# KMO_IO_MV2_9_min.net
KiCad netlist of a schematic drawn in EAGLE
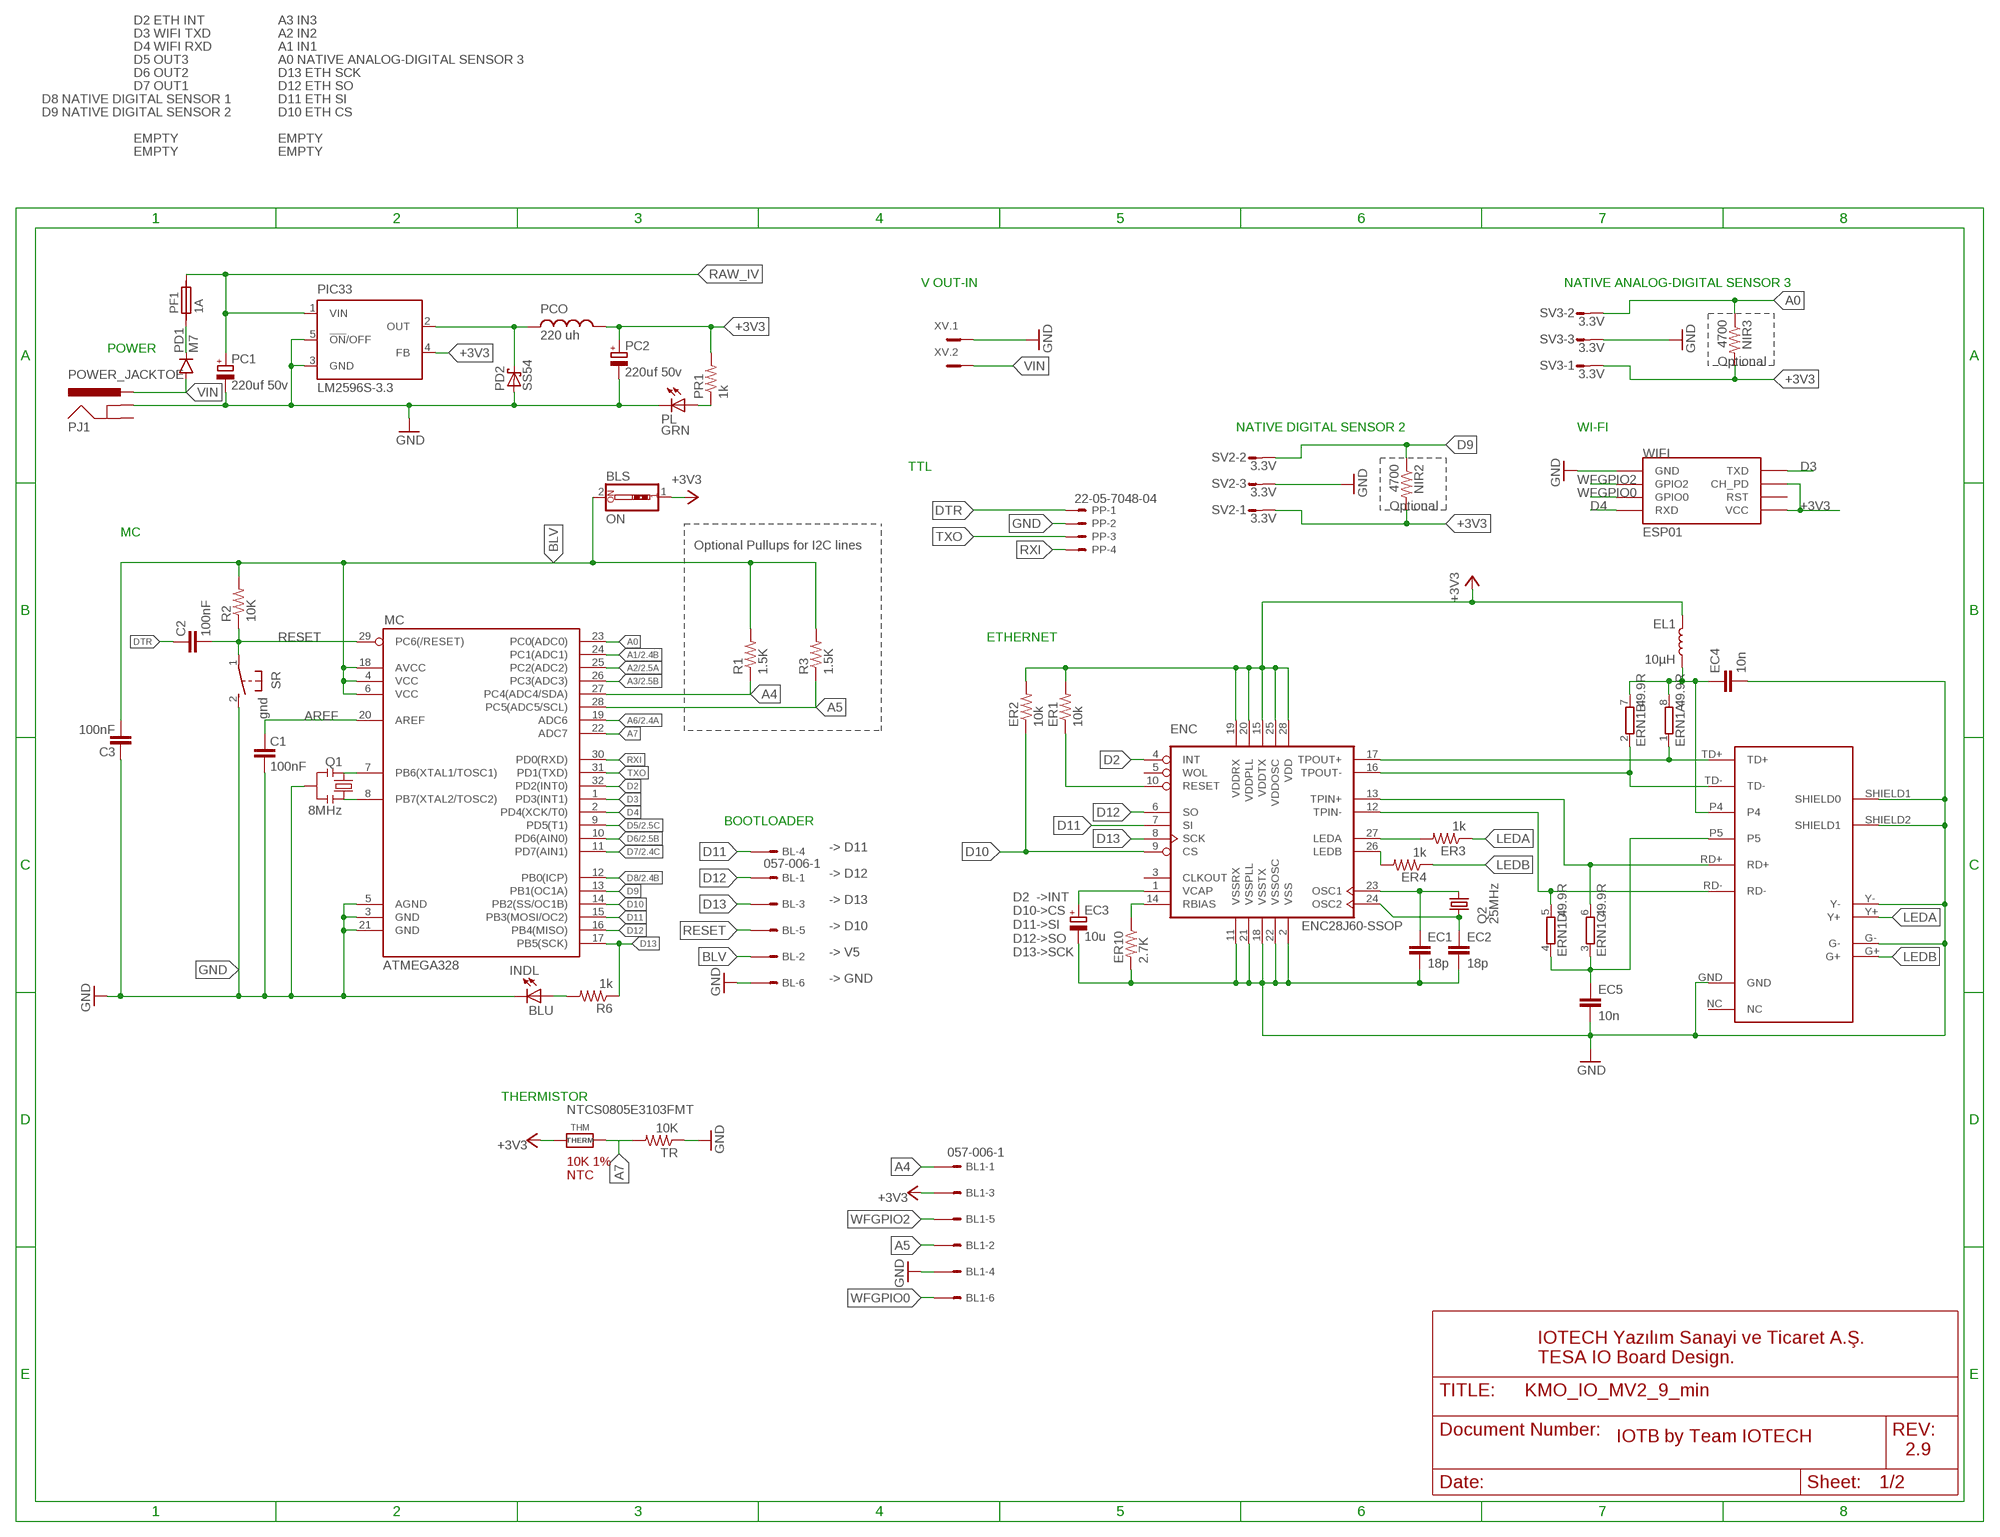
[diagram p0: schematic, sheet 1]
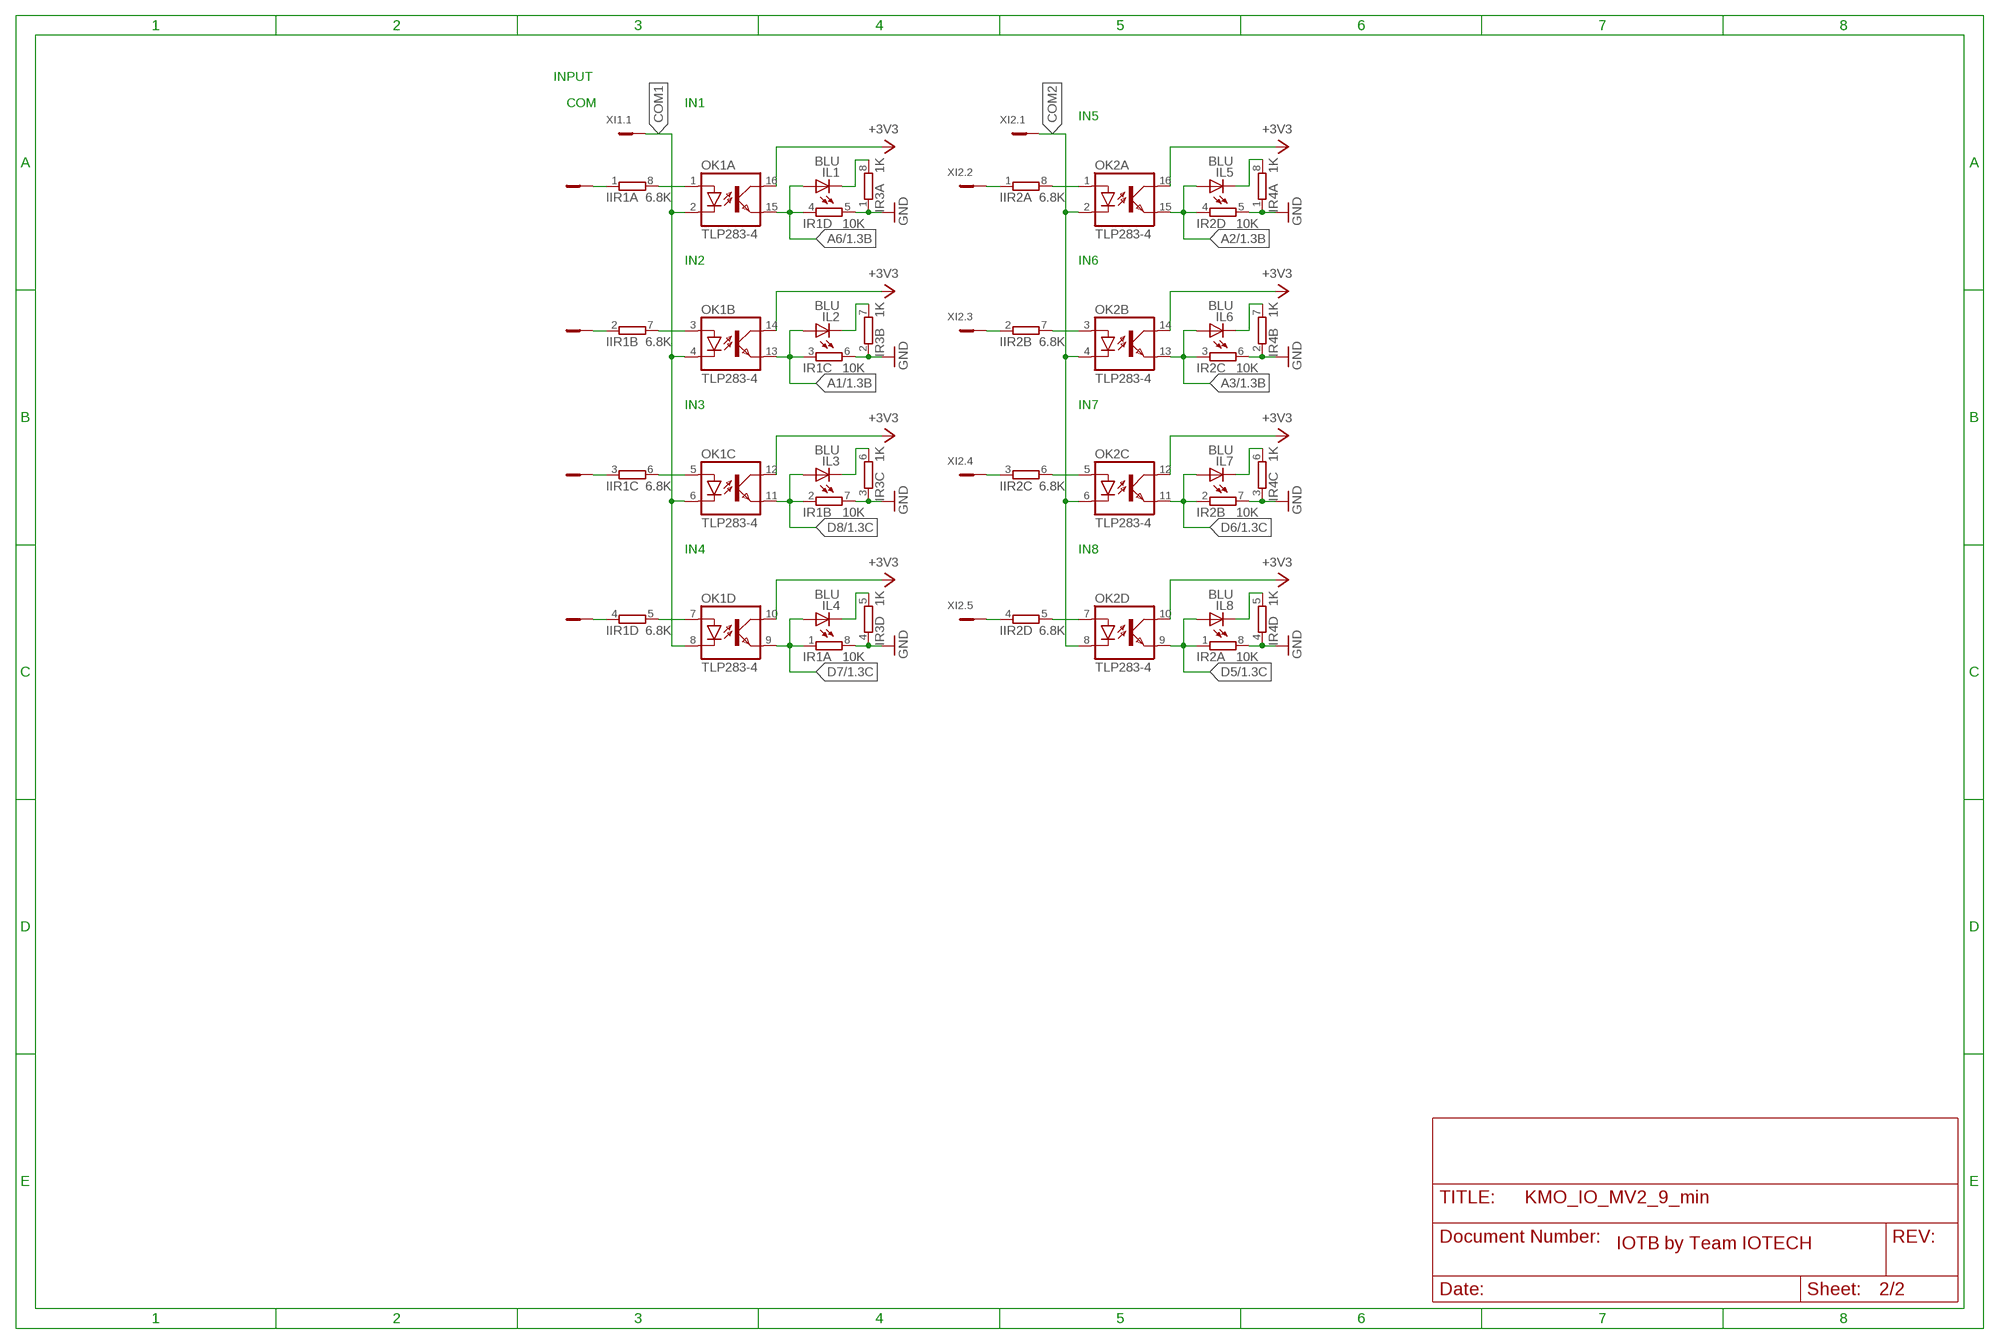
[diagram p1: schematic, sheet 2]

(export (version "E")
  (design (tool "Eeschema 10.0.6"))
  (components
    (comp (ref "BL")
      (value "057-006-1")
      (footprint "eagle-import:057-006-1")
      (libsource (lib "eagle-import") (part "057-006-1"))
    )
    (comp (ref "BL1")
      (value "057-006-1")
      (footprint "eagle-import:057-006-1")
      (libsource (lib "eagle-import") (part "057-006-1"))
    )
    (comp (ref "BLS")
      (value "ON")
      (footprint "eagle-import:EDG-01")
      (libsource (lib "eagle-import") (part "SW_DIP-1"))
    )
    (comp (ref "C1")
      (value "100nF")
      (footprint "eagle-import:0805")
      (libsource (lib "eagle-import") (part "CAP0805"))
    )
    (comp (ref "C2")
      (value "100nF")
      (footprint "eagle-import:0805")
      (libsource (lib "eagle-import") (part "CAP0805"))
    )
    (comp (ref "C3")
      (value "100nF")
      (footprint "eagle-import:0805")
      (libsource (lib "eagle-import") (part "CAP0805"))
    )
    (comp (ref "EC1")
      (value "18p")
      (footprint "eagle-import:0805")
      (libsource (lib "eagle-import") (part "CAP0805"))
    )
    (comp (ref "EC2")
      (value "18p")
      (footprint "eagle-import:0805")
      (libsource (lib "eagle-import") (part "CAP0805"))
    )
    (comp (ref "EC3")
      (value "10u")
      (footprint "eagle-import:CT3216")
      (libsource (lib "eagle-import") (part "CPOL-EUCT3216"))
    )
    (comp (ref "EC4")
      (value "10n")
      (footprint "eagle-import:0805")
      (libsource (lib "eagle-import") (part "CAP0805"))
    )
    (comp (ref "EC5")
      (value "10n")
      (footprint "eagle-import:0805")
      (libsource (lib "eagle-import") (part "CAP0805"))
    )
    (comp (ref "EL1")
      (value "10µH")
      (footprint "eagle-import:0805")
      (libsource (lib "eagle-import") (part "INDUCTOR-0805-3.3UH"))
    )
    (comp (ref "ENC")
      (value "ENC28J60-SSOP")
      (footprint "eagle-import:SSOP28")
      (libsource (lib "eagle-import") (part "ENC28J60-SSOP"))
    )
    (comp (ref "ER1")
      (value "10k")
      (footprint "eagle-import:0805")
      (libsource (lib "eagle-import") (part "RESISTOR0805-RES"))
    )
    (comp (ref "ER2")
      (value "10k")
      (footprint "eagle-import:0805")
      (libsource (lib "eagle-import") (part "RESISTOR0805-RES"))
    )
    (comp (ref "ER3")
      (value "1k")
      (footprint "eagle-import:0805")
      (libsource (lib "eagle-import") (part "RESISTOR0805-RES"))
    )
    (comp (ref "ER4")
      (value "1k")
      (footprint "eagle-import:0805")
      (libsource (lib "eagle-import") (part "RESISTOR0805-RES"))
    )
    (comp (ref "ER10")
      (value "2.7K")
      (footprint "eagle-import:0805")
      (libsource (lib "eagle-import") (part "RESISTOR0805-RES"))
    )
    (comp (ref "ERN1")
      (value "49.9R")
      (footprint "eagle-import:0603-ARV")
      (libsource (lib "eagle-import") (part "4R-N0603-ARV"))
    )
    (comp (ref "INDL")
      (value "BLU")
      (footprint "eagle-import:CHIP-LED0805")
      (libsource (lib "eagle-import") (part "LEDCHIP-LED0805"))
    )
    (comp (ref "MC")
      (value "ATMEGA328")
      (footprint "eagle-import:TQFP32-08")
      (libsource (lib "eagle-import") (part "ATMEGA168"))
    )
    (comp (ref "NIR2")
      (value "4700")
      (footprint "eagle-import:0805")
      (libsource (lib "eagle-import") (part "RESISTOR0805-RES"))
    )
    (comp (ref "NIR3")
      (value "4700")
      (footprint "eagle-import:0805")
      (libsource (lib "eagle-import") (part "RESISTOR0805-RES"))
    )
    (comp (ref "PC1")
      (value "220uf 50v")
      (footprint "eagle-import:140CLH-1010")
      (libsource (lib "eagle-import") (part "CPOL-EU140CLH-1010"))
    )
    (comp (ref "PC2")
      (value "220uf 50v")
      (footprint "eagle-import:140CLH-1010")
      (libsource (lib "eagle-import") (part "CPOL-EU140CLH-1010"))
    )
    (comp (ref "PCO")
      (value "220 uh")
      (footprint "eagle-import:MSS1260")
      (libsource (lib "eagle-import") (part "MSS1260"))
    )
    (comp (ref "PD1")
      (value "M7")
      (footprint "eagle-import:SMA-DIODE")
      (libsource (lib "eagle-import") (part "DIODESMA"))
    )
    (comp (ref "PD2")
      (value "SS54")
      (footprint "eagle-import:SMB")
      (libsource (lib "eagle-import") (part "SCHOTTKY-DIODESMD"))
    )
    (comp (ref "PF1")
      (value "1A")
      (footprint "eagle-import:1820")
      (libsource (lib "eagle-import") (part "SIBA194600"))
    )
    (comp (ref "PIC33")
      (value "LM2596S-3.3")
      (footprint "eagle-import:TO263-5")
      (fields
        (field (name "MF") "NATIONAL SEMICONDUCTOR")
        (field (name "MPN") "LM2596S-ADJ/NOPB")
        (field (name "SPICEPREFIX") "X")
      )
      (libsource (lib "eagle-import") (part "LM2596S"))
    )
    (comp (ref "PJ1")
      (value "POWER_JACKTOE")
      (footprint "eagle-import:POWER_JACK_SMD_OVERPASTE_TOE")
      (libsource (lib "eagle-import") (part "POWER_JACKTOE"))
    )
    (comp (ref "PL")
      (value "GRN")
      (footprint "eagle-import:CHIP-LED0805")
      (libsource (lib "eagle-import") (part "LEDCHIP-LED0805"))
    )
    (comp (ref "PP")
      (value "22-05-7048-04")
      (footprint "eagle-import:7395-04")
      (fields (field (name "MF") "MOLEX"))
      (libsource (lib "eagle-import") (part "22-?-0405-7048"))
    )
    (comp (ref "PR1")
      (value "1k")
      (footprint "eagle-import:0805")
      (libsource (lib "eagle-import") (part "RESISTOR0805-RES"))
    )
    (comp (ref "Q1")
      (value "8MHz")
      (footprint "eagle-import:RESONATOR-SMD-1_1")
      (libsource (lib "eagle-import") (part "RESONATOR1{colon}1"))
    )
    (comp (ref "Q2")
      (value "25MHz")
      (footprint "eagle-import:5.0X3.2_2")
      (libsource (lib "eagle-import") (part "KX-9B"))
    )
    (comp (ref "R1")
      (value "1.5K")
      (footprint "eagle-import:0805")
      (libsource (lib "eagle-import") (part "RESISTOR0805-RES"))
    )
    (comp (ref "R2")
      (value "10K")
      (footprint "eagle-import:0805")
      (libsource (lib "eagle-import") (part "RESISTOR0805-RES"))
    )
    (comp (ref "R3")
      (value "1.5K")
      (footprint "eagle-import:0805")
      (libsource (lib "eagle-import") (part "RESISTOR0805-RES"))
    )
    (comp (ref "R6")
      (value "1k")
      (footprint "eagle-import:0805")
      (libsource (lib "eagle-import") (part "RESISTOR0805-RES"))
    )
    (comp (ref "SR")
      (value "gnd")
      (footprint "eagle-import:B3F-31XX")
      (fields (field (name "MPN") "B3F-3100"))
      (libsource (lib "eagle-import") (part "31-XX"))
    )
    (comp (ref "SV2")
      (value "3.3V")
      (footprint "eagle-import:S03P")
      (libsource (lib "eagle-import") (part "S03P"))
    )
    (comp (ref "SV3")
      (value "3.3V")
      (footprint "eagle-import:S03P")
      (libsource (lib "eagle-import") (part "S03P"))
    )
    (comp (ref "THM")
      (value "THERM")
      (footprint "eagle-import:MICROBUILDER_0805_NOTHERMALS")
      (libsource (lib "eagle-import") (part "MICROBUILDER_RESISTOR0805_NOTHERMALS"))
    )
    (comp (ref "TR")
      (value "10K")
      (footprint "eagle-import:0805")
      (libsource (lib "eagle-import") (part "RESISTOR0805-RES"))
    )
    (comp (ref "U$2")
      (value "HR911105A")
      (footprint "eagle-import:RJ45")
      (libsource (lib "eagle-import") (part "HR911105A"))
    )
    (comp (ref "WIFI")
      (value "ESP01")
      (footprint "eagle-import:ESP01")
      (libsource (lib "eagle-import") (part "ESP01"))
    )
    (comp (ref "XV")
      (value "MC2")
      (footprint "eagle-import:MC2")
      (libsource (lib "eagle-import") (part "MC2"))
    )
    (comp (ref "IIR1")
      (value "6.8K")
      (footprint "eagle-import:0603-ARV")
      (libsource (lib "eagle-import") (part "4R-N0603-ARV"))
    )
    (comp (ref "IIR2")
      (value "6.8K")
      (footprint "eagle-import:0603-ARV")
      (libsource (lib "eagle-import") (part "4R-N0603-ARV"))
    )
    (comp (ref "IL1")
      (value "BLU")
      (footprint "eagle-import:CHIP-LED0805")
      (libsource (lib "eagle-import") (part "LEDCHIP-LED0805"))
    )
    (comp (ref "IL2")
      (value "BLU")
      (footprint "eagle-import:CHIP-LED0805")
      (libsource (lib "eagle-import") (part "LEDCHIP-LED0805"))
    )
    (comp (ref "IL3")
      (value "BLU")
      (footprint "eagle-import:CHIP-LED0805")
      (libsource (lib "eagle-import") (part "LEDCHIP-LED0805"))
    )
    (comp (ref "IL4")
      (value "BLU")
      (footprint "eagle-import:CHIP-LED0805")
      (libsource (lib "eagle-import") (part "LEDCHIP-LED0805"))
    )
    (comp (ref "IL5")
      (value "BLU")
      (footprint "eagle-import:CHIP-LED0805")
      (libsource (lib "eagle-import") (part "LEDCHIP-LED0805"))
    )
    (comp (ref "IL6")
      (value "BLU")
      (footprint "eagle-import:CHIP-LED0805")
      (libsource (lib "eagle-import") (part "LEDCHIP-LED0805"))
    )
    (comp (ref "IL7")
      (value "BLU")
      (footprint "eagle-import:CHIP-LED0805")
      (libsource (lib "eagle-import") (part "LEDCHIP-LED0805"))
    )
    (comp (ref "IL8")
      (value "BLU")
      (footprint "eagle-import:CHIP-LED0805")
      (libsource (lib "eagle-import") (part "LEDCHIP-LED0805"))
    )
    (comp (ref "IR1")
      (value "10K")
      (footprint "eagle-import:0603-ARV")
      (libsource (lib "eagle-import") (part "4R-N0603-ARV"))
    )
    (comp (ref "IR2")
      (value "10K")
      (footprint "eagle-import:0603-ARV")
      (libsource (lib "eagle-import") (part "4R-N0603-ARV"))
    )
    (comp (ref "IR3")
      (value "1K")
      (footprint "eagle-import:0603-ARV")
      (libsource (lib "eagle-import") (part "4R-N0603-ARV"))
    )
    (comp (ref "IR4")
      (value "1K")
      (footprint "eagle-import:0603-ARV")
      (libsource (lib "eagle-import") (part "4R-N0603-ARV"))
    )
    (comp (ref "OK1")
      (value "TLP283-4")
      (footprint "eagle-import:MINI-FLAT-16")
      (fields (field (name "SPICEPREFIX") "O"))
      (libsource (lib "eagle-import") (part "TLP283-4"))
    )
    (comp (ref "OK2")
      (value "TLP283-4")
      (footprint "eagle-import:MINI-FLAT-16")
      (fields (field (name "SPICEPREFIX") "O"))
      (libsource (lib "eagle-import") (part "TLP283-4"))
    )
    (comp (ref "XI1")
      (value "MC5")
      (footprint "eagle-import:MC5")
      (libsource (lib "eagle-import") (part "MC5"))
    )
    (comp (ref "XI2")
      (value "MC5")
      (footprint "eagle-import:MC5")
      (libsource (lib "eagle-import") (part "MC5"))
    )
  )
  (nets
    (net (code "1") (name "+3V3") (class "Default")
      (node (ref "BL1") (pin "3") (pinfunction "S_3") (pintype "passive"))
      (node (ref "BLS") (pin "1") (pinfunction "1_1") (pintype "passive"))
      (node (ref "EL1") (pin "1") (pinfunction "1_1") (pintype "passive"))
      (node (ref "ENC") (pin "15") (pinfunction "VDDTX_15") (pintype "power_in"))
      (node (ref "ENC") (pin "19") (pinfunction "VDDRX_19") (pintype "power_in"))
      (node (ref "ENC") (pin "20") (pinfunction "VDDPLL_20") (pintype "power_in"))
      (node (ref "ENC") (pin "25") (pinfunction "VDDOSC_25") (pintype "power_in"))
      (node (ref "ENC") (pin "28") (pinfunction "VDD_28") (pintype "power_in"))
      (node (ref "ER1") (pin "2") (pinfunction "2_2") (pintype "passive"))
      (node (ref "ER2") (pin "2") (pinfunction "2_2") (pintype "passive"))
      (node (ref "NIR2") (pin "2") (pinfunction "2_2") (pintype "passive"))
      (node (ref "NIR3") (pin "2") (pinfunction "2_2") (pintype "passive"))
      (node (ref "OK1") (pin "10") (pinfunction "COL_10") (pintype "passive"))
      (node (ref "OK1") (pin "12") (pinfunction "COL_12") (pintype "passive"))
      (node (ref "OK1") (pin "14") (pinfunction "COL_14") (pintype "passive"))
      (node (ref "OK1") (pin "16") (pinfunction "COL_16") (pintype "passive"))
      (node (ref "OK2") (pin "10") (pinfunction "COL_10") (pintype "passive"))
      (node (ref "OK2") (pin "12") (pinfunction "COL_12") (pintype "passive"))
      (node (ref "OK2") (pin "14") (pinfunction "COL_14") (pintype "passive"))
      (node (ref "OK2") (pin "16") (pinfunction "COL_16") (pintype "passive"))
      (node (ref "PC2") (pin "+") (pinfunction "+_+") (pintype "passive"))
      (node (ref "PCO") (pin "P$1") (pinfunction "P$1_P$1") (pintype "passive"))
      (node (ref "PIC33") (pin "4") (pinfunction "FB_4") (pintype "input"))
      (node (ref "PR1") (pin "2") (pinfunction "2_2") (pintype "passive"))
      (node (ref "SV2") (pin "1") (pinfunction "S_1") (pintype "passive"))
      (node (ref "SV3") (pin "1") (pinfunction "S_1") (pintype "passive"))
      (node (ref "THM") (pin "1") (pinfunction "1_1") (pintype "passive"))
      (node (ref "WIFI") (pin "CH_PD") (pinfunction "CH_PD_CH_PD") (pintype "bidirectional"))
      (node (ref "WIFI") (pin "VCC") (pinfunction "VCC_VCC") (pintype "bidirectional"))
    )
    (net (code "2") (name "A0") (class "Default")
      (node (ref "MC") (pin "23") (pinfunction "PC0(ADC0)_23") (pintype "bidirectional"))
      (node (ref "NIR3") (pin "1") (pinfunction "1_1") (pintype "passive"))
      (node (ref "SV3") (pin "2") (pinfunction "S_2") (pintype "passive"))
    )
    (net (code "3") (name "A1") (class "Default")
      (node (ref "IL2") (pin "A") (pinfunction "A_A") (pintype "passive"))
      (node (ref "IR1") (pin "3") (pinfunction "1_3") (pintype "passive"))
      (node (ref "MC") (pin "24") (pinfunction "PC1(ADC1)_24") (pintype "bidirectional"))
      (node (ref "OK1") (pin "13") (pinfunction "EMIT_13") (pintype "passive"))
    )
    (net (code "4") (name "A2") (class "Default")
      (node (ref "IL5") (pin "A") (pinfunction "A_A") (pintype "passive"))
      (node (ref "IR2") (pin "4") (pinfunction "1_4") (pintype "passive"))
      (node (ref "MC") (pin "25") (pinfunction "PC2(ADC2)_25") (pintype "bidirectional"))
      (node (ref "OK2") (pin "15") (pinfunction "EMIT_15") (pintype "passive"))
    )
    (net (code "5") (name "A3") (class "Default")
      (node (ref "IL6") (pin "A") (pinfunction "A_A") (pintype "passive"))
      (node (ref "IR2") (pin "3") (pinfunction "1_3") (pintype "passive"))
      (node (ref "MC") (pin "26") (pinfunction "PC3(ADC3)_26") (pintype "bidirectional"))
      (node (ref "OK2") (pin "13") (pinfunction "EMIT_13") (pintype "passive"))
    )
    (net (code "6") (name "A4") (class "Default")
      (node (ref "BL1") (pin "1") (pinfunction "S_1") (pintype "passive"))
      (node (ref "MC") (pin "27") (pinfunction "PC4(ADC4/SDA)_27") (pintype "bidirectional"))
      (node (ref "R1") (pin "1") (pinfunction "1_1") (pintype "passive"))
    )
    (net (code "7") (name "A5") (class "Default")
      (node (ref "BL1") (pin "2") (pinfunction "S_2") (pintype "passive"))
      (node (ref "MC") (pin "28") (pinfunction "PC5(ADC5/SCL)_28") (pintype "bidirectional"))
      (node (ref "R3") (pin "1") (pinfunction "1_1") (pintype "passive"))
    )
    (net (code "8") (name "A6") (class "Default")
      (node (ref "IL1") (pin "A") (pinfunction "A_A") (pintype "passive"))
      (node (ref "IR1") (pin "4") (pinfunction "1_4") (pintype "passive"))
      (node (ref "MC") (pin "19") (pinfunction "ADC6_19") (pintype "bidirectional"))
      (node (ref "OK1") (pin "15") (pinfunction "EMIT_15") (pintype "passive"))
    )
    (net (code "9") (name "A7") (class "Default")
      (node (ref "MC") (pin "22") (pinfunction "ADC7_22") (pintype "bidirectional"))
      (node (ref "THM") (pin "2") (pinfunction "2_2") (pintype "passive"))
      (node (ref "TR") (pin "2") (pinfunction "2_2") (pintype "passive"))
    )
    (net (code "10") (name "AREF") (class "Default")
      (node (ref "C1") (pin "2") (pinfunction "2_2") (pintype "passive"))
      (node (ref "MC") (pin "20") (pinfunction "AREF_20") (pintype "bidirectional"))
    )
    (net (code "11") (name "BLV") (class "Default")
      (node (ref "BL") (pin "2") (pinfunction "S_2") (pintype "passive"))
      (node (ref "BLS") (pin "2") (pinfunction "2_2") (pintype "passive"))
      (node (ref "C3") (pin "1") (pinfunction "1_1") (pintype "passive"))
      (node (ref "MC") (pin "18") (pinfunction "AVCC_18") (pintype "bidirectional"))
      (node (ref "MC") (pin "4") (pinfunction "VCC_4") (pintype "bidirectional"))
      (node (ref "MC") (pin "6") (pinfunction "VCC_6") (pintype "bidirectional"))
      (node (ref "R1") (pin "2") (pinfunction "2_2") (pintype "passive"))
      (node (ref "R2") (pin "2") (pinfunction "2_2") (pintype "passive"))
      (node (ref "R3") (pin "2") (pinfunction "2_2") (pintype "passive"))
    )
    (net (code "12") (name "COM1") (class "Default")
      (node (ref "OK1") (pin "2") (pinfunction "C_2") (pintype "passive"))
      (node (ref "OK1") (pin "4") (pinfunction "C_4") (pintype "passive"))
      (node (ref "OK1") (pin "6") (pinfunction "C_6") (pintype "passive"))
      (node (ref "OK1") (pin "8") (pinfunction "C_8") (pintype "passive"))
      (node (ref "XI1") (pin "1") (pinfunction "SK_1") (pintype "passive"))
    )
    (net (code "13") (name "COM2") (class "Default")
      (node (ref "OK2") (pin "2") (pinfunction "C_2") (pintype "passive"))
      (node (ref "OK2") (pin "4") (pinfunction "C_4") (pintype "passive"))
      (node (ref "OK2") (pin "6") (pinfunction "C_6") (pintype "passive"))
      (node (ref "OK2") (pin "8") (pinfunction "C_8") (pintype "passive"))
      (node (ref "XI2") (pin "1") (pinfunction "SK_1") (pintype "passive"))
    )
    (net (code "14") (name "D2") (class "Default")
      (node (ref "ENC") (pin "4") (pinfunction "INT_4") (pintype "output"))
      (node (ref "MC") (pin "32") (pinfunction "PD2(INT0)_32") (pintype "bidirectional"))
    )
    (net (code "15") (name "D3") (class "Default")
      (node (ref "MC") (pin "1") (pinfunction "PD3(INT1)_1") (pintype "bidirectional"))
      (node (ref "WIFI") (pin "TX") (pinfunction "TXD_TX") (pintype "bidirectional"))
    )
    (net (code "16") (name "D4") (class "Default")
      (node (ref "MC") (pin "2") (pinfunction "PD4(XCK/T0)_2") (pintype "bidirectional"))
      (node (ref "WIFI") (pin "RX") (pinfunction "RXD_RX") (pintype "bidirectional"))
    )
    (net (code "17") (name "D5") (class "Default")
      (node (ref "IL8") (pin "A") (pinfunction "A_A") (pintype "passive"))
      (node (ref "IR2") (pin "1") (pinfunction "1_1") (pintype "passive"))
      (node (ref "MC") (pin "9") (pinfunction "PD5(T1)_9") (pintype "bidirectional"))
      (node (ref "OK2") (pin "9") (pinfunction "EMIT_9") (pintype "passive"))
    )
    (net (code "18") (name "D6") (class "Default")
      (node (ref "IL7") (pin "A") (pinfunction "A_A") (pintype "passive"))
      (node (ref "IR2") (pin "2") (pinfunction "1_2") (pintype "passive"))
      (node (ref "MC") (pin "10") (pinfunction "PD6(AIN0)_10") (pintype "bidirectional"))
      (node (ref "OK2") (pin "11") (pinfunction "EMIT_11") (pintype "passive"))
    )
    (net (code "19") (name "D7") (class "Default")
      (node (ref "IL4") (pin "A") (pinfunction "A_A") (pintype "passive"))
      (node (ref "IR1") (pin "1") (pinfunction "1_1") (pintype "passive"))
      (node (ref "MC") (pin "11") (pinfunction "PD7(AIN1)_11") (pintype "bidirectional"))
      (node (ref "OK1") (pin "9") (pinfunction "EMIT_9") (pintype "passive"))
    )
    (net (code "20") (name "D8") (class "Default")
      (node (ref "IL3") (pin "A") (pinfunction "A_A") (pintype "passive"))
      (node (ref "IR1") (pin "2") (pinfunction "1_2") (pintype "passive"))
      (node (ref "MC") (pin "12") (pinfunction "PB0(ICP)_12") (pintype "bidirectional"))
      (node (ref "OK1") (pin "11") (pinfunction "EMIT_11") (pintype "passive"))
    )
    (net (code "21") (name "D9") (class "Default")
      (node (ref "MC") (pin "13") (pinfunction "PB1(OC1A)_13") (pintype "bidirectional"))
      (node (ref "NIR2") (pin "1") (pinfunction "1_1") (pintype "passive"))
      (node (ref "SV2") (pin "2") (pinfunction "S_2") (pintype "passive"))
    )
    (net (code "22") (name "D10") (class "Default")
      (node (ref "ENC") (pin "9") (pinfunction "CS_9") (pintype "input"))
      (node (ref "ER2") (pin "1") (pinfunction "1_1") (pintype "passive"))
      (node (ref "MC") (pin "14") (pinfunction "PB2(SS/OC1B)_14") (pintype "bidirectional"))
    )
    (net (code "23") (name "D11") (class "Default")
      (node (ref "BL") (pin "4") (pinfunction "S_4") (pintype "passive"))
      (node (ref "ENC") (pin "7") (pinfunction "SI_7") (pintype "input"))
      (node (ref "MC") (pin "15") (pinfunction "PB3(MOSI/OC2)_15") (pintype "bidirectional"))
    )
    (net (code "24") (name "D12") (class "Default")
      (node (ref "BL") (pin "1") (pinfunction "S_1") (pintype "passive"))
      (node (ref "ENC") (pin "6") (pinfunction "SO_6") (pintype "output"))
      (node (ref "MC") (pin "16") (pinfunction "PB4(MISO)_16") (pintype "bidirectional"))
    )
    (net (code "25") (name "D13") (class "Default")
      (node (ref "BL") (pin "3") (pinfunction "S_3") (pintype "passive"))
      (node (ref "ENC") (pin "8") (pinfunction "SCK_8") (pintype "input"))
      (node (ref "MC") (pin "17") (pinfunction "PB5(SCK)_17") (pintype "bidirectional"))
      (node (ref "R6") (pin "1") (pinfunction "1_1") (pintype "passive"))
    )
    (net (code "26") (name "DTR") (class "Default")
      (node (ref "C2") (pin "2") (pinfunction "2_2") (pintype "passive"))
      (node (ref "PP") (pin "1") (pinfunction "S_1") (pintype "passive"))
    )
    (net (code "27") (name "GND") (class "Default")
      (node (ref "BL") (pin "6") (pinfunction "S_6") (pintype "passive"))
      (node (ref "BL1") (pin "4") (pinfunction "S_4") (pintype "passive"))
      (node (ref "C1") (pin "1") (pinfunction "1_1") (pintype "passive"))
      (node (ref "C3") (pin "2") (pinfunction "2_2") (pintype "passive"))
      (node (ref "EC1") (pin "2") (pinfunction "2_2") (pintype "passive"))
      (node (ref "EC2") (pin "2") (pinfunction "2_2") (pintype "passive"))
      (node (ref "EC3") (pin "-") (pinfunction "-_-") (pintype "passive"))
      (node (ref "EC4") (pin "2") (pinfunction "2_2") (pintype "passive"))
      (node (ref "EC5") (pin "2") (pinfunction "2_2") (pintype "passive"))
      (node (ref "ENC") (pin "11") (pinfunction "VSSRX_11") (pintype "power_in"))
      (node (ref "ENC") (pin "18") (pinfunction "VSSTX_18") (pintype "power_in"))
      (node (ref "ENC") (pin "2") (pinfunction "VSS_2") (pintype "power_in"))
      (node (ref "ENC") (pin "21") (pinfunction "VSSPLL_21") (pintype "power_in"))
      (node (ref "ENC") (pin "22") (pinfunction "VSSOSC_22") (pintype "power_in"))
      (node (ref "ER10") (pin "2") (pinfunction "2_2") (pintype "passive"))
      (node (ref "INDL") (pin "C") (pinfunction "C_C") (pintype "passive"))
      (node (ref "IR1") (pin "5") (pinfunction "2_5") (pintype "passive"))
      (node (ref "IR1") (pin "6") (pinfunction "2_6") (pintype "passive"))
      (node (ref "IR1") (pin "7") (pinfunction "2_7") (pintype "passive"))
      (node (ref "IR1") (pin "8") (pinfunction "2_8") (pintype "passive"))
      (node (ref "IR2") (pin "5") (pinfunction "2_5") (pintype "passive"))
      (node (ref "IR2") (pin "6") (pinfunction "2_6") (pintype "passive"))
      (node (ref "IR2") (pin "7") (pinfunction "2_7") (pintype "passive"))
      (node (ref "IR2") (pin "8") (pinfunction "2_8") (pintype "passive"))
      (node (ref "IR3") (pin "1") (pinfunction "1_1") (pintype "passive"))
      (node (ref "IR3") (pin "2") (pinfunction "1_2") (pintype "passive"))
      (node (ref "IR3") (pin "3") (pinfunction "1_3") (pintype "passive"))
      (node (ref "IR3") (pin "4") (pinfunction "1_4") (pintype "passive"))
      (node (ref "IR4") (pin "1") (pinfunction "1_1") (pintype "passive"))
      (node (ref "IR4") (pin "2") (pinfunction "1_2") (pintype "passive"))
      (node (ref "IR4") (pin "3") (pinfunction "1_3") (pintype "passive"))
      (node (ref "IR4") (pin "4") (pinfunction "1_4") (pintype "passive"))
      (node (ref "MC") (pin "21") (pinfunction "GND_21") (pintype "bidirectional"))
      (node (ref "MC") (pin "3") (pinfunction "GND_3") (pintype "bidirectional"))
      (node (ref "MC") (pin "5") (pinfunction "AGND_5") (pintype "bidirectional"))
      (node (ref "PC1") (pin "-") (pinfunction "-_-") (pintype "passive"))
      (node (ref "PC2") (pin "-") (pinfunction "-_-") (pintype "passive"))
      (node (ref "PD2") (pin "A") (pinfunction "A_A") (pintype "passive"))
      (node (ref "PIC33") (pin "3") (pinfunction "GND_3") (pintype "power_in"))
      (node (ref "PIC33") (pin "5") (pinfunction "~{ON}/OFF_5") (pintype "input"))
      (node (ref "PJ1") (pin "GND") (pinfunction "GNDBREAK_GND") (pintype "bidirectional"))
      (node (ref "PL") (pin "C") (pinfunction "C_C") (pintype "passive"))
      (node (ref "PP") (pin "2") (pinfunction "S_2") (pintype "passive"))
      (node (ref "Q1") (pin "2") (pinfunction "2_2") (pintype "passive"))
      (node (ref "SR") (pin "2") (pinfunction "S_2") (pintype "passive"))
      (node (ref "SV2") (pin "3") (pinfunction "S_3") (pintype "passive"))
      (node (ref "SV3") (pin "3") (pinfunction "S_3") (pintype "passive"))
      (node (ref "TR") (pin "1") (pinfunction "1_1") (pintype "passive"))
      (node (ref "U$2") (pin "G-") (pinfunction "G-_G-") (pintype "bidirectional"))
      (node (ref "U$2") (pin "GND") (pinfunction "GND_GND") (pintype "bidirectional"))
      (node (ref "U$2") (pin "SHIELD1") (pinfunction "SHIELD0_SHIELD1") (pintype "bidirectional"))
      (node (ref "U$2") (pin "SHIELD2") (pinfunction "SHIELD1_SHIELD2") (pintype "bidirectional"))
      (node (ref "U$2") (pin "Y-") (pinfunction "Y-_Y-") (pintype "bidirectional"))
      (node (ref "WIFI") (pin "GND") (pinfunction "GND_GND") (pintype "bidirectional"))
      (node (ref "XV") (pin "1") (pinfunction "SK_1") (pintype "passive"))
    )
    (net (code "28") (name "LEDA") (class "Default")
      (node (ref "ER3") (pin "1") (pinfunction "1_1") (pintype "passive"))
      (node (ref "U$2") (pin "Y+") (pinfunction "Y+_Y+") (pintype "bidirectional"))
    )
    (net (code "29") (name "LEDB") (class "Default")
      (node (ref "ER4") (pin "1") (pinfunction "1_1") (pintype "passive"))
      (node (ref "U$2") (pin "G+") (pinfunction "G+_G+") (pintype "bidirectional"))
    )
    (net (code "30") (name "Net-(ENC-LEDA)") (class "Default")
      (node (ref "ENC") (pin "27") (pinfunction "LEDA_27") (pintype "output"))
      (node (ref "ER3") (pin "2") (pinfunction "2_2") (pintype "passive"))
    )
    (net (code "31") (name "Net-(ENC-LEDB)") (class "Default")
      (node (ref "ENC") (pin "26") (pinfunction "LEDB_26") (pintype "output"))
      (node (ref "ER4") (pin "2") (pinfunction "2_2") (pintype "passive"))
    )
    (net (code "32") (name "Net-(ENC-OSC1)") (class "Default")
      (node (ref "EC1") (pin "1") (pinfunction "1_1") (pintype "passive"))
      (node (ref "ENC") (pin "23") (pinfunction "OSC1_23") (pintype "input"))
      (node (ref "Q2") (pin "2") (pinfunction "2_2") (pintype "passive"))
    )
    (net (code "33") (name "Net-(ENC-OSC2)") (class "Default")
      (node (ref "EC2") (pin "1") (pinfunction "1_1") (pintype "passive"))
      (node (ref "ENC") (pin "24") (pinfunction "OSC2_24") (pintype "output"))
      (node (ref "Q2") (pin "1") (pinfunction "1_1") (pintype "passive"))
    )
    (net (code "34") (name "Net-(ENC-RBIAS)") (class "Default")
      (node (ref "ENC") (pin "14") (pinfunction "RBIAS_14") (pintype "passive"))
      (node (ref "ER10") (pin "1") (pinfunction "1_1") (pintype "passive"))
    )
    (net (code "35") (name "Net-(ENC-RESET)") (class "Default")
      (node (ref "ENC") (pin "10") (pinfunction "RESET_10") (pintype "input"))
      (node (ref "ER1") (pin "1") (pinfunction "1_1") (pintype "passive"))
    )
    (net (code "36") (name "Net-(ENC-TPIN+)") (class "Default")
      (node (ref "ENC") (pin "13") (pinfunction "TPIN+_13") (pintype "input"))
      (node (ref "ERN1") (pin "6") (pinfunction "2_6") (pintype "passive"))
      (node (ref "U$2") (pin "RD+") (pinfunction "RD+_RD+") (pintype "bidirectional"))
    )
    (net (code "37") (name "Net-(ENC-TPIN-)") (class "Default")
      (node (ref "ENC") (pin "12") (pinfunction "TPIN-_12") (pintype "input"))
      (node (ref "ERN1") (pin "5") (pinfunction "2_5") (pintype "passive"))
      (node (ref "U$2") (pin "RD-") (pinfunction "RD-_RD-") (pintype "bidirectional"))
    )
    (net (code "38") (name "Net-(ENC-TPOUT+)") (class "Default")
      (node (ref "ENC") (pin "17") (pinfunction "TPOUT+_17") (pintype "output"))
      (node (ref "ERN1") (pin "1") (pinfunction "1_1") (pintype "passive"))
      (node (ref "U$2") (pin "TD+") (pinfunction "TD+_TD+") (pintype "bidirectional"))
    )
    (net (code "39") (name "Net-(ENC-TPOUT-)") (class "Default")
      (node (ref "ENC") (pin "16") (pinfunction "TPOUT-_16") (pintype "output"))
      (node (ref "ERN1") (pin "2") (pinfunction "1_2") (pintype "passive"))
      (node (ref "U$2") (pin "TD-") (pinfunction "TD-_TD-") (pintype "bidirectional"))
    )
    (net (code "40") (name "Net-(ENC-VCAP)") (class "Default")
      (node (ref "EC3") (pin "+") (pinfunction "+_+") (pintype "passive"))
      (node (ref "ENC") (pin "1") (pinfunction "VCAP_1") (pintype "power_in"))
    )
    (net (code "41") (name "Net-(ERN1A-2)") (class "Default")
      (node (ref "EC4") (pin "1") (pinfunction "1_1") (pintype "passive"))
      (node (ref "EL1") (pin "2") (pinfunction "2_2") (pintype "passive"))
      (node (ref "ERN1") (pin "7") (pinfunction "2_7") (pintype "passive"))
      (node (ref "ERN1") (pin "8") (pinfunction "2_8") (pintype "passive"))
      (node (ref "U$2") (pin "P4") (pinfunction "P4_P4") (pintype "bidirectional"))
    )
    (net (code "42") (name "Net-(ERN1C-1)") (class "Default")
      (node (ref "EC5") (pin "1") (pinfunction "1_1") (pintype "passive"))
      (node (ref "ERN1") (pin "3") (pinfunction "1_3") (pintype "passive"))
      (node (ref "ERN1") (pin "4") (pinfunction "1_4") (pintype "passive"))
      (node (ref "U$2") (pin "P5") (pinfunction "P5_P5") (pintype "bidirectional"))
    )
    (net (code "43") (name "Net-(IIR1A-2)") (class "Default")
      (node (ref "IIR1") (pin "8") (pinfunction "2_8") (pintype "passive"))
      (node (ref "OK1") (pin "1") (pinfunction "A_1") (pintype "passive"))
    )
    (net (code "44") (name "Net-(IIR1B-1)") (class "Default")
      (node (ref "IIR1") (pin "2") (pinfunction "1_2") (pintype "passive"))
      (node (ref "XI1") (pin "3") (pinfunction "SK_3") (pintype "passive"))
    )
    (net (code "45") (name "Net-(IIR1B-2)") (class "Default")
      (node (ref "IIR1") (pin "7") (pinfunction "2_7") (pintype "passive"))
      (node (ref "OK1") (pin "3") (pinfunction "A_3") (pintype "passive"))
    )
    (net (code "46") (name "Net-(IIR1C-1)") (class "Default")
      (node (ref "IIR1") (pin "3") (pinfunction "1_3") (pintype "passive"))
      (node (ref "XI1") (pin "4") (pinfunction "SK_4") (pintype "passive"))
    )
    (net (code "47") (name "Net-(IIR1C-2)") (class "Default")
      (node (ref "IIR1") (pin "6") (pinfunction "2_6") (pintype "passive"))
      (node (ref "OK1") (pin "5") (pinfunction "A_5") (pintype "passive"))
    )
    (net (code "48") (name "Net-(IIR1D-1)") (class "Default")
      (node (ref "IIR1") (pin "4") (pinfunction "1_4") (pintype "passive"))
      (node (ref "XI1") (pin "5") (pinfunction "SK_5") (pintype "passive"))
    )
    (net (code "49") (name "Net-(IIR1D-2)") (class "Default")
      (node (ref "IIR1") (pin "5") (pinfunction "2_5") (pintype "passive"))
      (node (ref "OK1") (pin "7") (pinfunction "A_7") (pintype "passive"))
    )
    (net (code "50") (name "Net-(IIR2A-2)") (class "Default")
      (node (ref "IIR2") (pin "8") (pinfunction "2_8") (pintype "passive"))
      (node (ref "OK2") (pin "1") (pinfunction "A_1") (pintype "passive"))
    )
    (net (code "51") (name "Net-(IIR2B-1)") (class "Default")
      (node (ref "IIR2") (pin "2") (pinfunction "1_2") (pintype "passive"))
      (node (ref "XI2") (pin "3") (pinfunction "SK_3") (pintype "passive"))
    )
    (net (code "52") (name "Net-(IIR2B-2)") (class "Default")
      (node (ref "IIR2") (pin "7") (pinfunction "2_7") (pintype "passive"))
      (node (ref "OK2") (pin "3") (pinfunction "A_3") (pintype "passive"))
    )
    (net (code "53") (name "Net-(IIR2C-1)") (class "Default")
      (node (ref "IIR2") (pin "3") (pinfunction "1_3") (pintype "passive"))
      (node (ref "XI2") (pin "4") (pinfunction "SK_4") (pintype "passive"))
    )
    (net (code "54") (name "Net-(IIR2C-2)") (class "Default")
      (node (ref "IIR2") (pin "6") (pinfunction "2_6") (pintype "passive"))
      (node (ref "OK2") (pin "5") (pinfunction "A_5") (pintype "passive"))
    )
    (net (code "55") (name "Net-(IIR2D-1)") (class "Default")
      (node (ref "IIR2") (pin "4") (pinfunction "1_4") (pintype "passive"))
      (node (ref "XI2") (pin "5") (pinfunction "SK_5") (pintype "passive"))
    )
    (net (code "56") (name "Net-(IIR2D-2)") (class "Default")
      (node (ref "IIR2") (pin "5") (pinfunction "2_5") (pintype "passive"))
      (node (ref "OK2") (pin "7") (pinfunction "A_7") (pintype "passive"))
    )
    (net (code "57") (name "Net-(INDL-PadA)") (class "Default")
      (node (ref "INDL") (pin "A") (pinfunction "A_A") (pintype "passive"))
      (node (ref "R6") (pin "2") (pinfunction "2_2") (pintype "passive"))
    )
    (net (code "58") (name "Net-(IR3A-2)") (class "Default")
      (node (ref "IL1") (pin "C") (pinfunction "C_C") (pintype "passive"))
      (node (ref "IR3") (pin "8") (pinfunction "2_8") (pintype "passive"))
    )
    (net (code "59") (name "Net-(IR3B-2)") (class "Default")
      (node (ref "IL2") (pin "C") (pinfunction "C_C") (pintype "passive"))
      (node (ref "IR3") (pin "7") (pinfunction "2_7") (pintype "passive"))
    )
    (net (code "60") (name "Net-(IR3C-2)") (class "Default")
      (node (ref "IL3") (pin "C") (pinfunction "C_C") (pintype "passive"))
      (node (ref "IR3") (pin "6") (pinfunction "2_6") (pintype "passive"))
    )
    (net (code "61") (name "Net-(IR3D-2)") (class "Default")
      (node (ref "IL4") (pin "C") (pinfunction "C_C") (pintype "passive"))
      (node (ref "IR3") (pin "5") (pinfunction "2_5") (pintype "passive"))
    )
    (net (code "62") (name "Net-(IR4A-2)") (class "Default")
      (node (ref "IL5") (pin "C") (pinfunction "C_C") (pintype "passive"))
      (node (ref "IR4") (pin "8") (pinfunction "2_8") (pintype "passive"))
    )
    (net (code "63") (name "Net-(IR4B-2)") (class "Default")
      (node (ref "IL6") (pin "C") (pinfunction "C_C") (pintype "passive"))
      (node (ref "IR4") (pin "7") (pinfunction "2_7") (pintype "passive"))
    )
    (net (code "64") (name "Net-(IR4C-2)") (class "Default")
      (node (ref "IL7") (pin "C") (pinfunction "C_C") (pintype "passive"))
      (node (ref "IR4") (pin "6") (pinfunction "2_6") (pintype "passive"))
    )
    (net (code "65") (name "Net-(IR4D-2)") (class "Default")
      (node (ref "IL8") (pin "C") (pinfunction "C_C") (pintype "passive"))
      (node (ref "IR4") (pin "5") (pinfunction "2_5") (pintype "passive"))
    )
    (net (code "66") (name "Net-(MC-PB6(XTAL1{slash}TOSC1))") (class "Default")
      (node (ref "MC") (pin "7") (pinfunction "PB6(XTAL1/TOSC1)_7") (pintype "bidirectional"))
      (node (ref "Q1") (pin "1") (pinfunction "1_1") (pintype "passive"))
    )
    (net (code "67") (name "Net-(MC-PB7(XTAL2{slash}TOSC2))") (class "Default")
      (node (ref "MC") (pin "8") (pinfunction "PB7(XTAL2/TOSC2)_8") (pintype "bidirectional"))
      (node (ref "Q1") (pin "3") (pinfunction "3_3") (pintype "passive"))
    )
    (net (code "68") (name "Net-(PD1-PadC)") (class "Default")
      (node (ref "PD1") (pin "C") (pinfunction "C_C") (pintype "passive"))
      (node (ref "PF1") (pin "1") (pinfunction "1_1") (pintype "passive"))
    )
    (net (code "69") (name "Net-(PIC33-OUT)") (class "Default")
      (node (ref "PCO") (pin "P$2") (pinfunction "P$2_P$2") (pintype "passive"))
      (node (ref "PD2") (pin "C") (pinfunction "C_C") (pintype "passive"))
      (node (ref "PIC33") (pin "2") (pinfunction "OUT_2") (pintype "output"))
    )
    (net (code "70") (name "Net-(PL-PadA)") (class "Default")
      (node (ref "PL") (pin "A") (pinfunction "A_A") (pintype "passive"))
      (node (ref "PR1") (pin "1") (pinfunction "1_1") (pintype "passive"))
    )
    (net (code "71") (name "Net-(XI1B-SK)") (class "Default")
      (node (ref "IIR1") (pin "1") (pinfunction "1_1") (pintype "passive"))
      (node (ref "XI1") (pin "2") (pinfunction "SK_2") (pintype "passive"))
    )
    (net (code "72") (name "Net-(XI2B-SK)") (class "Default")
      (node (ref "IIR2") (pin "1") (pinfunction "1_1") (pintype "passive"))
      (node (ref "XI2") (pin "2") (pinfunction "SK_2") (pintype "passive"))
    )
    (net (code "73") (name "RAW_IV") (class "Default")
      (node (ref "PC1") (pin "+") (pinfunction "+_+") (pintype "passive"))
      (node (ref "PF1") (pin "2") (pinfunction "2_2") (pintype "passive"))
      (node (ref "PIC33") (pin "1") (pinfunction "VIN_1") (pintype "input"))
    )
    (net (code "74") (name "RESET") (class "Default")
      (node (ref "BL") (pin "5") (pinfunction "S_5") (pintype "passive"))
      (node (ref "C2") (pin "1") (pinfunction "1_1") (pintype "passive"))
      (node (ref "MC") (pin "29") (pinfunction "PC6(/RESET)_29") (pintype "bidirectional"))
      (node (ref "R2") (pin "1") (pinfunction "1_1") (pintype "passive"))
      (node (ref "SR") (pin "1") (pinfunction "P_1") (pintype "passive"))
    )
    (net (code "75") (name "RXI") (class "Default")
      (node (ref "MC") (pin "30") (pinfunction "PD0(RXD)_30") (pintype "bidirectional"))
      (node (ref "PP") (pin "4") (pinfunction "S_4") (pintype "passive"))
    )
    (net (code "76") (name "TXO") (class "Default")
      (node (ref "MC") (pin "31") (pinfunction "PD1(TXD)_31") (pintype "bidirectional"))
      (node (ref "PP") (pin "3") (pinfunction "S_3") (pintype "passive"))
    )
    (net (code "77") (name "VIN") (class "Default")
      (node (ref "PD1") (pin "A") (pinfunction "A_A") (pintype "passive"))
      (node (ref "PJ1") (pin "VIN0") (pinfunction "PWR_VIN0") (pintype "bidirectional"))
      (node (ref "XV") (pin "2") (pinfunction "SK_2") (pintype "passive"))
    )
    (net (code "78") (name "WFGPIO0") (class "Default")
      (node (ref "BL1") (pin "6") (pinfunction "S_6") (pintype "passive"))
      (node (ref "WIFI") (pin "GPIO0") (pinfunction "GPIO0_GPIO0") (pintype "bidirectional"))
    )
    (net (code "79") (name "WFGPIO2") (class "Default")
      (node (ref "BL1") (pin "5") (pinfunction "S_5") (pintype "passive"))
      (node (ref "WIFI") (pin "GPIO2") (pinfunction "GPIO2_GPIO2") (pintype "bidirectional"))
    )
    (net (code "80") (name "unconnected-(ENC-CLKOUT-Pad3)") (class "Default")
      (node (ref "ENC") (pin "3") (pinfunction "CLKOUT_3") (pintype "output"))
    )
    (net (code "81") (name "unconnected-(ENC-WOL-Pad5)") (class "Default")
      (node (ref "ENC") (pin "5") (pinfunction "WOL_5") (pintype "output"))
    )
    (net (code "82") (name "unconnected-(PJ1-GND-PadP$4)") (class "Default")
      (node (ref "PJ1") (pin "P$4") (pinfunction "GND_P$4") (pintype "bidirectional"))
    )
    (net (code "83") (name "unconnected-(U$2-PadNC)") (class "Default")
      (node (ref "U$2") (pin "NC") (pinfunction "NC_NC") (pintype "bidirectional"))
    )
    (net (code "84") (name "unconnected-(WIFI-PadRST)") (class "Default")
      (node (ref "WIFI") (pin "RST") (pinfunction "RST_RST") (pintype "bidirectional"))
    )
  )
)
